# synth-zodiac-aries-vcf.net
KiCad netlist of a schematic drawn in EAGLE
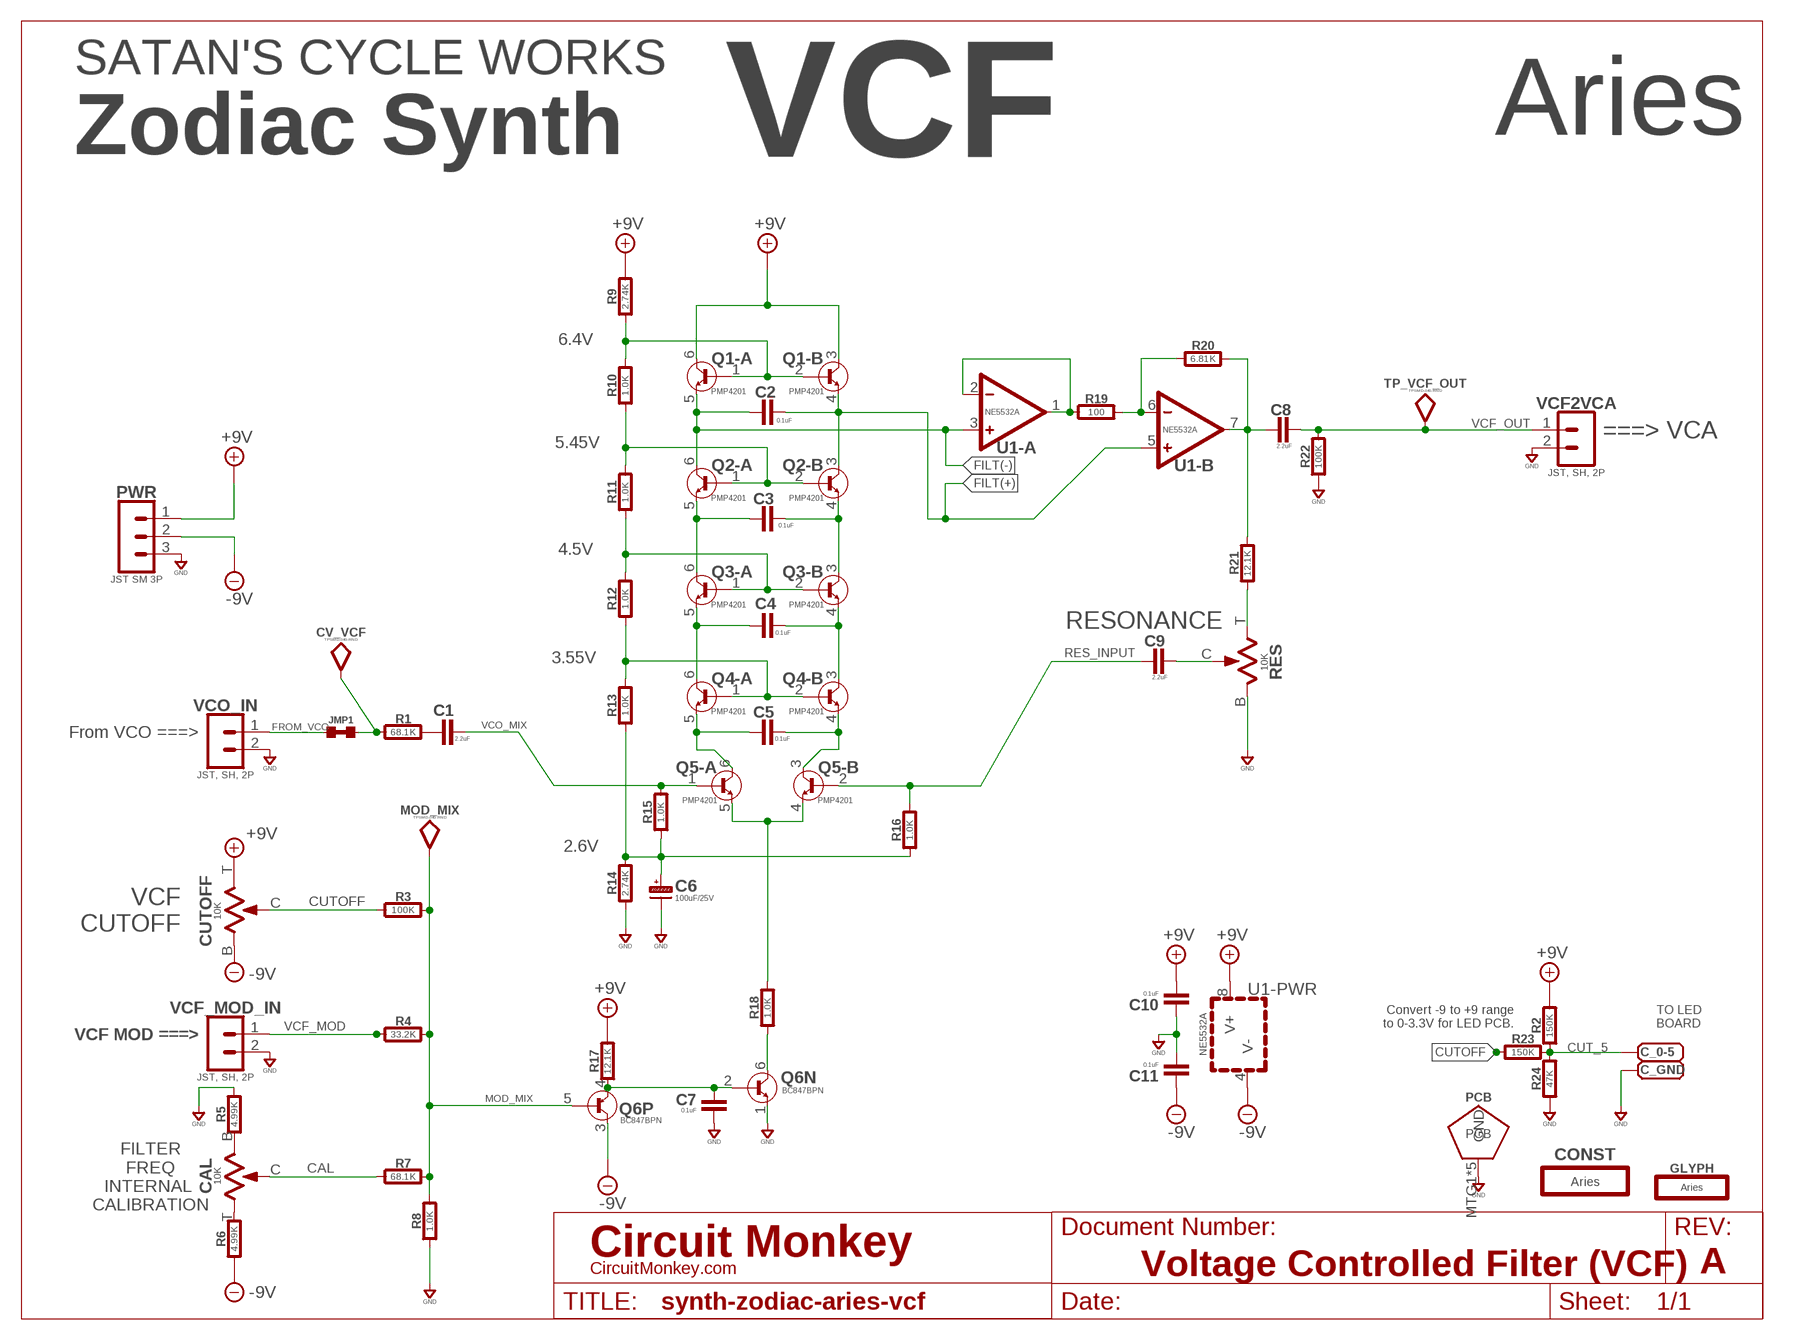
[diagram p0: schematic, sheet 1]

(export (version "E")
  (design (tool "Eeschema 10.0.6"))
  (components
    (comp (ref "C1")
      (value "2.2uF")
      (footprint "eagle-import:0603-CAP")
      (libsource (lib "eagle-import") (part "CAPACITOR0603"))
    )
    (comp (ref "C2")
      (value "0.1uF")
      (footprint "eagle-import:0603-CAP")
      (libsource (lib "eagle-import") (part "CAPACITOR0603"))
    )
    (comp (ref "C3")
      (value "0.1uF")
      (footprint "eagle-import:0603-CAP")
      (libsource (lib "eagle-import") (part "CAPACITOR0603"))
    )
    (comp (ref "C4")
      (value "0.1uF")
      (footprint "eagle-import:0603-CAP")
      (libsource (lib "eagle-import") (part "CAPACITOR0603"))
    )
    (comp (ref "C5")
      (value "0.1uF")
      (footprint "eagle-import:0603-CAP")
      (libsource (lib "eagle-import") (part "CAPACITOR0603"))
    )
    (comp (ref "C6")
      (value "100uF/25V")
      (footprint "eagle-import:CAP_ALUM_SMT_6.3")
      (fields
        (field (name "COST01") "0.5")
        (field (name "COST10") "0.5")
        (field (name "COST100") "0.4")
        (field (name "MFR") "Wurth")
        (field (name "MPN") "865090445008")
      )
      (libsource (lib "eagle-import") (part "CAPACITOR_POL-ALUM-SMT-6.3"))
    )
    (comp (ref "C7")
      (value "0.1uF")
      (footprint "eagle-import:0603-CAP")
      (libsource (lib "eagle-import") (part "CAPACITOR0603"))
    )
    (comp (ref "C8")
      (value "2.2uF")
      (footprint "eagle-import:0603-CAP")
      (libsource (lib "eagle-import") (part "CAPACITOR0603"))
    )
    (comp (ref "C9")
      (value "2.2uF")
      (footprint "eagle-import:0603-CAP")
      (libsource (lib "eagle-import") (part "CAPACITOR0603"))
    )
    (comp (ref "C10")
      (value "0.1uF")
      (footprint "eagle-import:0603-CAP")
      (libsource (lib "eagle-import") (part "CAPACITOR0603"))
    )
    (comp (ref "C11")
      (value "0.1uF")
      (footprint "eagle-import:0603-CAP")
      (libsource (lib "eagle-import") (part "CAPACITOR0603"))
    )
    (comp (ref "CAL")
      (value "10K")
      (footprint "eagle-import:TRIM_BOURNS_TC33X")
      (fields (field (name "MFR") "Bourns") (field (name "MPN") "TC33X"))
      (libsource (lib "eagle-import") (part "TRIMPOTTC33X"))
    )
    (comp (ref "CONST")
      (value "Aries")
      (footprint "eagle-import:ARIES-CONST")
      (libsource (lib "eagle-import") (part "CONSTELLATION-ARIES"))
    )
    (comp (ref "CUTOFF")
      (value "10K")
      (footprint "eagle-import:POT-RV9110")
      (fields (field (name "MFR") "Tayda") (field (name "MPN") "RV9110NO-OS15A00"))
      (libsource (lib "eagle-import") (part "TRIMPOT9MM_PCB_SHAFT"))
    )
    (comp (ref "CV_VCF")
      (value "TPSMD-040-RND")
      (footprint "eagle-import:SMD-040MIL-RND")
      (libsource (lib "eagle-import") (part "TPSMD-040-RND"))
    )
    (comp (ref "C_0-5")
      (value "PADSMD-070X070")
      (footprint "eagle-import:SMD-070MIL")
      (libsource (lib "eagle-import") (part "PADSMD-070X070"))
    )
    (comp (ref "C_GND")
      (value "PADSMD-070X070")
      (footprint "eagle-import:SMD-070MIL")
      (libsource (lib "eagle-import") (part "PADSMD-070X070"))
    )
    (comp (ref "GLYPH")
      (value "Aries")
      (footprint "eagle-import:ARIES-GLYPH")
      (libsource (lib "eagle-import") (part "GLYPH-ARIES"))
    )
    (comp (ref "JMP1")
      (value "NP")
      (footprint "eagle-import:0603-SHORT")
      (libsource (lib "eagle-import") (part "SHORT0603"))
    )
    (comp (ref "MOD_MIX")
      (value "TPSMD-040-RND")
      (footprint "eagle-import:SMD-040MIL-RND")
      (libsource (lib "eagle-import") (part "TPSMD-040-RND"))
    )
    (comp (ref "PCB")
      (value "PCB FAB")
      (footprint "eagle-import:PENTAGON-40MM-RAD")
      (libsource (lib "eagle-import") (part "PENTAGON-40R"))
    )
    (comp (ref "PWR")
      (value "JST SM 3P")
      (footprint "eagle-import:BM03B-SRSS-TB")
      (fields (field (name "MFR") "JST") (field (name "MPN") "BM03B-SRSS-TB"))
      (libsource (lib "eagle-import") (part "03P-SM-VT-SMT"))
    )
    (comp (ref "Q1")
      (value "PMP4201")
      (footprint "eagle-import:SOT666")
      (fields (field (name "MFR") "NXP") (field (name "MPN") "PMP4201V"))
      (libsource (lib "eagle-import") (part "NPN-DUALPMP4201"))
    )
    (comp (ref "Q2")
      (value "PMP4201")
      (footprint "eagle-import:SOT666")
      (fields (field (name "MFR") "NXP") (field (name "MPN") "PMP4201V"))
      (libsource (lib "eagle-import") (part "NPN-DUALPMP4201"))
    )
    (comp (ref "Q3")
      (value "PMP4201")
      (footprint "eagle-import:SOT666")
      (fields (field (name "MFR") "NXP") (field (name "MPN") "PMP4201V"))
      (libsource (lib "eagle-import") (part "NPN-DUALPMP4201"))
    )
    (comp (ref "Q4")
      (value "PMP4201")
      (footprint "eagle-import:SOT666")
      (fields (field (name "MFR") "NXP") (field (name "MPN") "PMP4201V"))
      (libsource (lib "eagle-import") (part "NPN-DUALPMP4201"))
    )
    (comp (ref "Q5")
      (value "PMP4201")
      (footprint "eagle-import:SOT666")
      (fields (field (name "MFR") "NXP") (field (name "MPN") "PMP4201V"))
      (libsource (lib "eagle-import") (part "NPN-DUALPMP4201"))
    )
    (comp (ref "Q6")
      (value "BC847BPN")
      (footprint "eagle-import:SOT363")
      (fields (field (name "MFR") "PANJIT") (field (name "MPN") "BC487BPN"))
      (libsource (lib "eagle-import") (part "NPN-PNPBC847BPN"))
    )
    (comp (ref "R1")
      (value "68.1K")
      (footprint "eagle-import:0603-RES")
      (libsource (lib "eagle-import") (part "RESISTOR0603"))
    )
    (comp (ref "R2")
      (value "150K")
      (footprint "eagle-import:0603-RES")
      (libsource (lib "eagle-import") (part "RESISTOR0603"))
    )
    (comp (ref "R3")
      (value "100K")
      (footprint "eagle-import:0603-RES")
      (libsource (lib "eagle-import") (part "RESISTOR0603"))
    )
    (comp (ref "R4")
      (value "33.2K")
      (footprint "eagle-import:0603-RES")
      (libsource (lib "eagle-import") (part "RESISTOR0603"))
    )
    (comp (ref "R5")
      (value "4.99K")
      (footprint "eagle-import:0603-RES")
      (libsource (lib "eagle-import") (part "RESISTOR0603"))
    )
    (comp (ref "R6")
      (value "4.99K")
      (footprint "eagle-import:0603-RES")
      (libsource (lib "eagle-import") (part "RESISTOR0603"))
    )
    (comp (ref "R7")
      (value "68.1K")
      (footprint "eagle-import:0603-RES")
      (libsource (lib "eagle-import") (part "RESISTOR0603"))
    )
    (comp (ref "R8")
      (value "1.0K")
      (footprint "eagle-import:0603-RES")
      (libsource (lib "eagle-import") (part "RESISTOR0603"))
    )
    (comp (ref "R9")
      (value "2.74K")
      (footprint "eagle-import:0603-RES")
      (libsource (lib "eagle-import") (part "RESISTOR0603"))
    )
    (comp (ref "R10")
      (value "1.0K")
      (footprint "eagle-import:0603-RES")
      (libsource (lib "eagle-import") (part "RESISTOR0603"))
    )
    (comp (ref "R11")
      (value "1.0K")
      (footprint "eagle-import:0603-RES")
      (libsource (lib "eagle-import") (part "RESISTOR0603"))
    )
    (comp (ref "R12")
      (value "1.0K")
      (footprint "eagle-import:0603-RES")
      (libsource (lib "eagle-import") (part "RESISTOR0603"))
    )
    (comp (ref "R13")
      (value "1.0K")
      (footprint "eagle-import:0603-RES")
      (libsource (lib "eagle-import") (part "RESISTOR0603"))
    )
    (comp (ref "R14")
      (value "2.74K")
      (footprint "eagle-import:0603-RES")
      (libsource (lib "eagle-import") (part "RESISTOR0603"))
    )
    (comp (ref "R15")
      (value "1.0K")
      (footprint "eagle-import:0603-RES")
      (libsource (lib "eagle-import") (part "RESISTOR0603"))
    )
    (comp (ref "R16")
      (value "1.0K")
      (footprint "eagle-import:0603-RES")
      (libsource (lib "eagle-import") (part "RESISTOR0603"))
    )
    (comp (ref "R17")
      (value "12.1K")
      (footprint "eagle-import:0603-RES")
      (libsource (lib "eagle-import") (part "RESISTOR0603"))
    )
    (comp (ref "R18")
      (value "1.0K")
      (footprint "eagle-import:0603-RES")
      (libsource (lib "eagle-import") (part "RESISTOR0603"))
    )
    (comp (ref "R19")
      (value "100")
      (footprint "eagle-import:0603-RES")
      (libsource (lib "eagle-import") (part "RESISTOR0603"))
    )
    (comp (ref "R20")
      (value "6.81K")
      (footprint "eagle-import:0603-RES")
      (libsource (lib "eagle-import") (part "RESISTOR0603"))
    )
    (comp (ref "R21")
      (value "12.1K")
      (footprint "eagle-import:0603-RES")
      (libsource (lib "eagle-import") (part "RESISTOR0603"))
    )
    (comp (ref "R22")
      (value "100K")
      (footprint "eagle-import:0603-RES")
      (libsource (lib "eagle-import") (part "RESISTOR0603"))
    )
    (comp (ref "R23")
      (value "150K")
      (footprint "eagle-import:0603-RES")
      (libsource (lib "eagle-import") (part "RESISTOR0603"))
    )
    (comp (ref "R24")
      (value "47K")
      (footprint "eagle-import:0603-RES")
      (libsource (lib "eagle-import") (part "RESISTOR0603"))
    )
    (comp (ref "RES")
      (value "10K")
      (footprint "eagle-import:POT-RV9110")
      (fields (field (name "MFR") "Tayda") (field (name "MPN") "RV9110NO-OS15A00"))
      (libsource (lib "eagle-import") (part "TRIMPOT9MM_PCB_SHAFT"))
    )
    (comp (ref "TP_VCF_OUT")
      (value "TPSMD-040-RND")
      (footprint "eagle-import:SMD-040MIL-RND")
      (libsource (lib "eagle-import") (part "TPSMD-040-RND"))
    )
    (comp (ref "U1")
      (value "NE5532A")
      (footprint "eagle-import:SOP08")
      (fields (field (name "MFR") "TI") (field (name "MPN") "NE5532DR"))
      (libsource (lib "eagle-import") (part "DUALNE5532-SMD"))
    )
    (comp (ref "VCF2VCA")
      (value "JST, SH, 2P")
      (footprint "eagle-import:BM02B-SRSS-TB")
      (fields (field (name "MFR") "JST") (field (name "MPN") "BMB02B-SRSS-TB"))
      (libsource (lib "eagle-import") (part "02P-SM-VT-SMT"))
    )
    (comp (ref "VCF_MOD_IN")
      (value "JST, SH, 2P")
      (footprint "eagle-import:BM02B-SRSS-TB")
      (fields (field (name "MFR") "JST") (field (name "MPN") "BMB02B-SRSS-TB"))
      (libsource (lib "eagle-import") (part "02P-SM-VT-SMT"))
    )
    (comp (ref "VCO_IN")
      (value "JST, SH, 2P")
      (footprint "eagle-import:BM02B-SRSS-TB")
      (fields (field (name "MFR") "JST") (field (name "MPN") "BMB02B-SRSS-TB"))
      (libsource (lib "eagle-import") (part "02P-SM-VT-SMT"))
    )
  )
  (nets
    (net (code "1") (name "+9V") (class "Default")
      (node (ref "C10") (pin "2") (pinfunction "2_2") (pintype "passive"))
      (node (ref "CUTOFF") (pin "T") (pinfunction "3_T") (pintype "passive"))
      (node (ref "PWR") (pin "1") (pinfunction "1_1") (pintype "passive"))
      (node (ref "Q1") (pin "3") (pinfunction "COLLECTOR_3") (pintype "bidirectional"))
      (node (ref "Q1") (pin "6") (pinfunction "COLLECTOR_6") (pintype "bidirectional"))
      (node (ref "R17") (pin "2") (pinfunction "2_2") (pintype "passive"))
      (node (ref "R2") (pin "2") (pinfunction "2_2") (pintype "passive"))
      (node (ref "R9") (pin "2") (pinfunction "2_2") (pintype "passive"))
      (node (ref "U1") (pin "8") (pinfunction "V+_8") (pintype "power_in"))
    )
    (net (code "2") (name "-9V") (class "Default")
      (node (ref "C11") (pin "1") (pinfunction "1_1") (pintype "passive"))
      (node (ref "CUTOFF") (pin "B") (pinfunction "1_B") (pintype "passive"))
      (node (ref "PWR") (pin "2") (pinfunction "2_2") (pintype "passive"))
      (node (ref "Q6") (pin "3") (pinfunction "COLLECTOR_3") (pintype "bidirectional"))
      (node (ref "R6") (pin "1") (pinfunction "1_1") (pintype "passive"))
      (node (ref "U1") (pin "4") (pinfunction "V-_4") (pintype "power_in"))
    )
    (net (code "3") (name "/CAL") (class "Default")
      (node (ref "CAL") (pin "C") (pinfunction "2_C") (pintype "passive"))
      (node (ref "R7") (pin "1") (pinfunction "1_1") (pintype "passive"))
    )
    (net (code "4") (name "/CUT_5") (class "Default")
      (node (ref "C_0-5") (pin "1") (pinfunction "PAD_1") (pintype "bidirectional"))
      (node (ref "R2") (pin "1") (pinfunction "1_1") (pintype "passive"))
      (node (ref "R23") (pin "2") (pinfunction "2_2") (pintype "passive"))
      (node (ref "R24") (pin "2") (pinfunction "2_2") (pintype "passive"))
    )
    (net (code "5") (name "/FROM_VCO") (class "Default")
      (node (ref "JMP1") (pin "3") (pinfunction "1_3") (pintype "passive"))
      (node (ref "VCO_IN") (pin "1") (pinfunction "1_1") (pintype "passive"))
    )
    (net (code "6") (name "/MOD_MIX") (class "Default")
      (node (ref "MOD_MIX") (pin "TP") (pinfunction "P$1_TP") (pintype "bidirectional"))
      (node (ref "Q6") (pin "5") (pinfunction "BASE_5") (pintype "bidirectional"))
      (node (ref "R3") (pin "2") (pinfunction "2_2") (pintype "passive"))
      (node (ref "R4") (pin "2") (pinfunction "2_2") (pintype "passive"))
      (node (ref "R7") (pin "2") (pinfunction "2_2") (pintype "passive"))
      (node (ref "R8") (pin "2") (pinfunction "2_2") (pintype "passive"))
    )
    (net (code "7") (name "/RES_INPUT") (class "Default")
      (node (ref "C9") (pin "1") (pinfunction "1_1") (pintype "passive"))
      (node (ref "Q5") (pin "2") (pinfunction "BASE_2") (pintype "bidirectional"))
      (node (ref "R16") (pin "2") (pinfunction "2_2") (pintype "passive"))
    )
    (net (code "8") (name "/VCF_MOD") (class "Default")
      (node (ref "R4") (pin "1") (pinfunction "1_1") (pintype "passive"))
      (node (ref "VCF_MOD_IN") (pin "1") (pinfunction "1_1") (pintype "passive"))
    )
    (net (code "9") (name "/VCF_OUT") (class "Default")
      (node (ref "C8") (pin "2") (pinfunction "2_2") (pintype "passive"))
      (node (ref "R22") (pin "2") (pinfunction "2_2") (pintype "passive"))
      (node (ref "TP_VCF_OUT") (pin "TP") (pinfunction "P$1_TP") (pintype "bidirectional"))
      (node (ref "VCF2VCA") (pin "1") (pinfunction "1_1") (pintype "passive"))
    )
    (net (code "10") (name "/VCO_MIX") (class "Default")
      (node (ref "C1") (pin "2") (pinfunction "2_2") (pintype "passive"))
      (node (ref "Q5") (pin "1") (pinfunction "BASE_1") (pintype "bidirectional"))
      (node (ref "R15") (pin "2") (pinfunction "2_2") (pintype "passive"))
    )
    (net (code "11") (name "CUTOFF") (class "Default")
      (node (ref "CUTOFF") (pin "C") (pinfunction "2_C") (pintype "passive"))
      (node (ref "R23") (pin "1") (pinfunction "1_1") (pintype "passive"))
      (node (ref "R3") (pin "1") (pinfunction "1_1") (pintype "passive"))
    )
    (net (code "12") (name "FILT(+)") (class "Default")
      (node (ref "C2") (pin "2") (pinfunction "2_2") (pintype "passive"))
      (node (ref "Q1") (pin "4") (pinfunction "EMITTER_4") (pintype "bidirectional"))
      (node (ref "Q2") (pin "3") (pinfunction "COLLECTOR_3") (pintype "bidirectional"))
      (node (ref "U1") (pin "5") (pinfunction "+_5") (pintype "input"))
    )
    (net (code "13") (name "FILT(-)") (class "Default")
      (node (ref "C2") (pin "1") (pinfunction "1_1") (pintype "passive"))
      (node (ref "Q1") (pin "5") (pinfunction "EMITTER_5") (pintype "bidirectional"))
      (node (ref "Q2") (pin "6") (pinfunction "COLLECTOR_6") (pintype "bidirectional"))
      (node (ref "U1") (pin "3") (pinfunction "+_3") (pintype "input"))
    )
    (net (code "14") (name "GND") (class "Default")
      (node (ref "C10") (pin "1") (pinfunction "1_1") (pintype "passive"))
      (node (ref "C11") (pin "2") (pinfunction "2_2") (pintype "passive"))
      (node (ref "C6") (pin "-") (pinfunction "N_-") (pintype "bidirectional"))
      (node (ref "C7") (pin "2") (pinfunction "2_2") (pintype "passive"))
      (node (ref "C_GND") (pin "1") (pinfunction "PAD_1") (pintype "bidirectional"))
      (node (ref "PCB") (pin "MTG1") (pinfunction "GND_MTG1") (pintype "bidirectional"))
      (node (ref "PCB") (pin "MTG2") (pinfunction "GND_MTG2") (pintype "bidirectional"))
      (node (ref "PCB") (pin "MTG3") (pinfunction "GND_MTG3") (pintype "bidirectional"))
      (node (ref "PCB") (pin "MTG4") (pinfunction "GND_MTG4") (pintype "bidirectional"))
      (node (ref "PCB") (pin "MTG5") (pinfunction "GND_MTG5") (pintype "bidirectional"))
      (node (ref "PWR") (pin "3") (pinfunction "3_3") (pintype "passive"))
      (node (ref "Q6") (pin "1") (pinfunction "EMITTER_1") (pintype "bidirectional"))
      (node (ref "R14") (pin "1") (pinfunction "1_1") (pintype "passive"))
      (node (ref "R22") (pin "1") (pinfunction "1_1") (pintype "passive"))
      (node (ref "R24") (pin "1") (pinfunction "1_1") (pintype "passive"))
      (node (ref "R5") (pin "2") (pinfunction "2_2") (pintype "passive"))
      (node (ref "R8") (pin "1") (pinfunction "1_1") (pintype "passive"))
      (node (ref "RES") (pin "B") (pinfunction "1_B") (pintype "passive"))
      (node (ref "VCF2VCA") (pin "2") (pinfunction "2_2") (pintype "passive"))
      (node (ref "VCF_MOD_IN") (pin "2") (pinfunction "2_2") (pintype "passive"))
      (node (ref "VCO_IN") (pin "2") (pinfunction "2_2") (pintype "passive"))
    )
    (net (code "15") (name "Net-(C1-Pad1)") (class "Default")
      (node (ref "C1") (pin "1") (pinfunction "1_1") (pintype "passive"))
      (node (ref "R1") (pin "2") (pinfunction "2_2") (pintype "passive"))
    )
    (net (code "16") (name "Net-(C6-P)") (class "Default")
      (node (ref "C6") (pin "+") (pinfunction "P_+") (pintype "bidirectional"))
      (node (ref "R13") (pin "1") (pinfunction "1_1") (pintype "passive"))
      (node (ref "R14") (pin "2") (pinfunction "2_2") (pintype "passive"))
      (node (ref "R15") (pin "1") (pinfunction "1_1") (pintype "passive"))
      (node (ref "R16") (pin "1") (pinfunction "1_1") (pintype "passive"))
    )
    (net (code "17") (name "Net-(CAL-1)") (class "Default")
      (node (ref "CAL") (pin "B") (pinfunction "1_B") (pintype "passive"))
      (node (ref "R5") (pin "1") (pinfunction "1_1") (pintype "passive"))
    )
    (net (code "18") (name "Net-(CAL-3)") (class "Default")
      (node (ref "CAL") (pin "T") (pinfunction "3_T") (pintype "passive"))
      (node (ref "R6") (pin "2") (pinfunction "2_2") (pintype "passive"))
    )
    (net (code "19") (name "Net-(CV_VCF-P$1)") (class "Default")
      (node (ref "CV_VCF") (pin "TP") (pinfunction "P$1_TP") (pintype "bidirectional"))
      (node (ref "JMP1") (pin "4") (pinfunction "2_4") (pintype "passive"))
      (node (ref "R1") (pin "1") (pinfunction "1_1") (pintype "passive"))
    )
    (net (code "20") (name "Net-(Q1A-BASE)") (class "Default")
      (node (ref "Q1") (pin "1") (pinfunction "BASE_1") (pintype "bidirectional"))
      (node (ref "Q1") (pin "2") (pinfunction "BASE_2") (pintype "bidirectional"))
      (node (ref "R10") (pin "2") (pinfunction "2_2") (pintype "passive"))
      (node (ref "R9") (pin "1") (pinfunction "1_1") (pintype "passive"))
    )
    (net (code "21") (name "Net-(Q2A-BASE)") (class "Default")
      (node (ref "Q2") (pin "1") (pinfunction "BASE_1") (pintype "bidirectional"))
      (node (ref "Q2") (pin "2") (pinfunction "BASE_2") (pintype "bidirectional"))
      (node (ref "R10") (pin "1") (pinfunction "1_1") (pintype "passive"))
      (node (ref "R11") (pin "2") (pinfunction "2_2") (pintype "passive"))
    )
    (net (code "22") (name "Net-(Q2A-EMITTER)") (class "Default")
      (node (ref "C3") (pin "1") (pinfunction "1_1") (pintype "passive"))
      (node (ref "Q2") (pin "5") (pinfunction "EMITTER_5") (pintype "bidirectional"))
      (node (ref "Q3") (pin "6") (pinfunction "COLLECTOR_6") (pintype "bidirectional"))
    )
    (net (code "23") (name "Net-(Q2B-EMITTER)") (class "Default")
      (node (ref "C3") (pin "2") (pinfunction "2_2") (pintype "passive"))
      (node (ref "Q2") (pin "4") (pinfunction "EMITTER_4") (pintype "bidirectional"))
      (node (ref "Q3") (pin "3") (pinfunction "COLLECTOR_3") (pintype "bidirectional"))
    )
    (net (code "24") (name "Net-(Q3A-BASE)") (class "Default")
      (node (ref "Q3") (pin "1") (pinfunction "BASE_1") (pintype "bidirectional"))
      (node (ref "Q3") (pin "2") (pinfunction "BASE_2") (pintype "bidirectional"))
      (node (ref "R11") (pin "1") (pinfunction "1_1") (pintype "passive"))
      (node (ref "R12") (pin "2") (pinfunction "2_2") (pintype "passive"))
    )
    (net (code "25") (name "Net-(Q3A-EMITTER)") (class "Default")
      (node (ref "C4") (pin "1") (pinfunction "1_1") (pintype "passive"))
      (node (ref "Q3") (pin "5") (pinfunction "EMITTER_5") (pintype "bidirectional"))
      (node (ref "Q4") (pin "6") (pinfunction "COLLECTOR_6") (pintype "bidirectional"))
    )
    (net (code "26") (name "Net-(Q3B-EMITTER)") (class "Default")
      (node (ref "C4") (pin "2") (pinfunction "2_2") (pintype "passive"))
      (node (ref "Q3") (pin "4") (pinfunction "EMITTER_4") (pintype "bidirectional"))
      (node (ref "Q4") (pin "3") (pinfunction "COLLECTOR_3") (pintype "bidirectional"))
    )
    (net (code "27") (name "Net-(Q4A-BASE)") (class "Default")
      (node (ref "Q4") (pin "1") (pinfunction "BASE_1") (pintype "bidirectional"))
      (node (ref "Q4") (pin "2") (pinfunction "BASE_2") (pintype "bidirectional"))
      (node (ref "R12") (pin "1") (pinfunction "1_1") (pintype "passive"))
      (node (ref "R13") (pin "2") (pinfunction "2_2") (pintype "passive"))
    )
    (net (code "28") (name "Net-(Q4A-EMITTER)") (class "Default")
      (node (ref "C5") (pin "1") (pinfunction "1_1") (pintype "passive"))
      (node (ref "Q4") (pin "5") (pinfunction "EMITTER_5") (pintype "bidirectional"))
      (node (ref "Q5") (pin "6") (pinfunction "COLLECTOR_6") (pintype "bidirectional"))
    )
    (net (code "29") (name "Net-(Q4B-EMITTER)") (class "Default")
      (node (ref "C5") (pin "2") (pinfunction "2_2") (pintype "passive"))
      (node (ref "Q4") (pin "4") (pinfunction "EMITTER_4") (pintype "bidirectional"))
      (node (ref "Q5") (pin "3") (pinfunction "COLLECTOR_3") (pintype "bidirectional"))
    )
    (net (code "30") (name "Net-(Q5A-EMITTER)") (class "Default")
      (node (ref "Q5") (pin "4") (pinfunction "EMITTER_4") (pintype "bidirectional"))
      (node (ref "Q5") (pin "5") (pinfunction "EMITTER_5") (pintype "bidirectional"))
      (node (ref "R18") (pin "2") (pinfunction "2_2") (pintype "passive"))
    )
    (net (code "31") (name "Net-(Q6A-BASE)") (class "Default")
      (node (ref "C7") (pin "1") (pinfunction "1_1") (pintype "passive"))
      (node (ref "Q6") (pin "2") (pinfunction "BASE_2") (pintype "bidirectional"))
      (node (ref "Q6") (pin "4") (pinfunction "EMITTER_4") (pintype "bidirectional"))
      (node (ref "R17") (pin "1") (pinfunction "1_1") (pintype "passive"))
    )
    (net (code "32") (name "Net-(Q6A-COLLECTOR)") (class "Default")
      (node (ref "Q6") (pin "6") (pinfunction "COLLECTOR_6") (pintype "bidirectional"))
      (node (ref "R18") (pin "1") (pinfunction "1_1") (pintype "passive"))
    )
    (net (code "33") (name "Net-(RES-2)") (class "Default")
      (node (ref "C9") (pin "2") (pinfunction "2_2") (pintype "passive"))
      (node (ref "RES") (pin "C") (pinfunction "2_C") (pintype "passive"))
    )
    (net (code "34") (name "Net-(RES-3)") (class "Default")
      (node (ref "R21") (pin "1") (pinfunction "1_1") (pintype "passive"))
      (node (ref "RES") (pin "T") (pinfunction "3_T") (pintype "passive"))
    )
    (net (code "35") (name "Net-(U1A--)") (class "Default")
      (node (ref "R19") (pin "1") (pinfunction "1_1") (pintype "passive"))
      (node (ref "U1") (pin "1") (pinfunction "OUT_1") (pintype "output"))
      (node (ref "U1") (pin "2") (pinfunction "-_2") (pintype "input"))
    )
    (net (code "36") (name "Net-(U1B--)") (class "Default")
      (node (ref "R19") (pin "2") (pinfunction "2_2") (pintype "passive"))
      (node (ref "R20") (pin "1") (pinfunction "1_1") (pintype "passive"))
      (node (ref "U1") (pin "6") (pinfunction "-_6") (pintype "input"))
    )
    (net (code "37") (name "Net-(U1B-OUT)") (class "Default")
      (node (ref "C8") (pin "1") (pinfunction "1_1") (pintype "passive"))
      (node (ref "R20") (pin "2") (pinfunction "2_2") (pintype "passive"))
      (node (ref "R21") (pin "2") (pinfunction "2_2") (pintype "passive"))
      (node (ref "U1") (pin "7") (pinfunction "OUT_7") (pintype "output"))
    )
  )
)
